# isp_attinyx4_dip_adapter.net
KiCad netlist of a schematic drawn in EAGLE
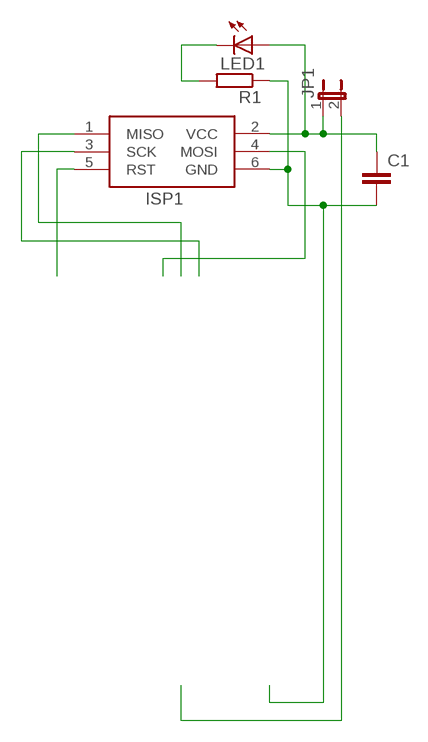
[diagram p0: schematic, sheet 1]

(export (version "E")
  (design (tool "Eeschema 10.0.6"))
  (components
    (comp (ref "C1")
      (value "C-EUC0805K")
      (footprint "eagle-import:C0805K")
      (libsource (lib "eagle-import") (part "C-EUC0805K"))
    )
    (comp (ref "ISP1")
      (value "AVRISP-6")
      (footprint "eagle-import:AVRISP")
      (libsource (lib "eagle-import") (part "AVRISP-6"))
    )
    (comp (ref "JP1")
      (value "JUMPER-2SMD-NO")
      (footprint "eagle-import:SJ_2S-NO")
      (libsource (lib "eagle-import") (part "JUMPER-2SMD-NO"))
    )
    (comp (ref "LED1")
      (value "LEDCHIPLED_0805")
      (footprint "eagle-import:CHIPLED_0805")
      (libsource (lib "eagle-import") (part "LEDCHIPLED_0805"))
    )
    (comp (ref "R1")
      (value "R-EU_R0805")
      (footprint "eagle-import:R0805")
      (libsource (lib "eagle-import") (part "R-EU_R0805"))
    )
  )
  (nets
    (net (code "1") (name "Net-(ISP1-GND)") (class "Default")
      (node (ref "C1") (pin "2") (pinfunction "2_2") (pintype "passive"))
      (node (ref "ISP1") (pin "6") (pinfunction "GND_6") (pintype "power_in"))
      (node (ref "R1") (pin "1") (pinfunction "1_1") (pintype "passive"))
    )
    (net (code "2") (name "Net-(ISP1-VCC)") (class "Default")
      (node (ref "C1") (pin "1") (pinfunction "1_1") (pintype "passive"))
      (node (ref "ISP1") (pin "2") (pinfunction "VCC_2") (pintype "power_in"))
      (node (ref "JP1") (pin "1") (pinfunction "1_1") (pintype "passive"))
      (node (ref "LED1") (pin "A") (pinfunction "A_A") (pintype "passive"))
    )
    (net (code "3") (name "Net-(LED1-PadC)") (class "Default")
      (node (ref "LED1") (pin "C") (pinfunction "C_C") (pintype "passive"))
      (node (ref "R1") (pin "2") (pinfunction "2_2") (pintype "passive"))
    )
    (net (code "4") (name "unconnected-(ISP1-MISO-Pad1)") (class "Default")
      (node (ref "ISP1") (pin "1") (pinfunction "MISO_1") (pintype "input"))
    )
    (net (code "5") (name "unconnected-(ISP1-MOSI-Pad4)") (class "Default")
      (node (ref "ISP1") (pin "4") (pinfunction "MOSI_4") (pintype "output"))
    )
    (net (code "6") (name "unconnected-(ISP1-RST-Pad5)") (class "Default")
      (node (ref "ISP1") (pin "5") (pinfunction "RST_5") (pintype "output"))
    )
    (net (code "7") (name "unconnected-(ISP1-SCK-Pad3)") (class "Default")
      (node (ref "ISP1") (pin "3") (pinfunction "SCK_3") (pintype "output"))
    )
    (net (code "8") (name "unconnected-(JP1-Pad2)") (class "Default")
      (node (ref "JP1") (pin "2") (pinfunction "2_2") (pintype "passive"))
    )
  )
)
